# trx.net
KiCad netlist of a schematic drawn in EAGLE
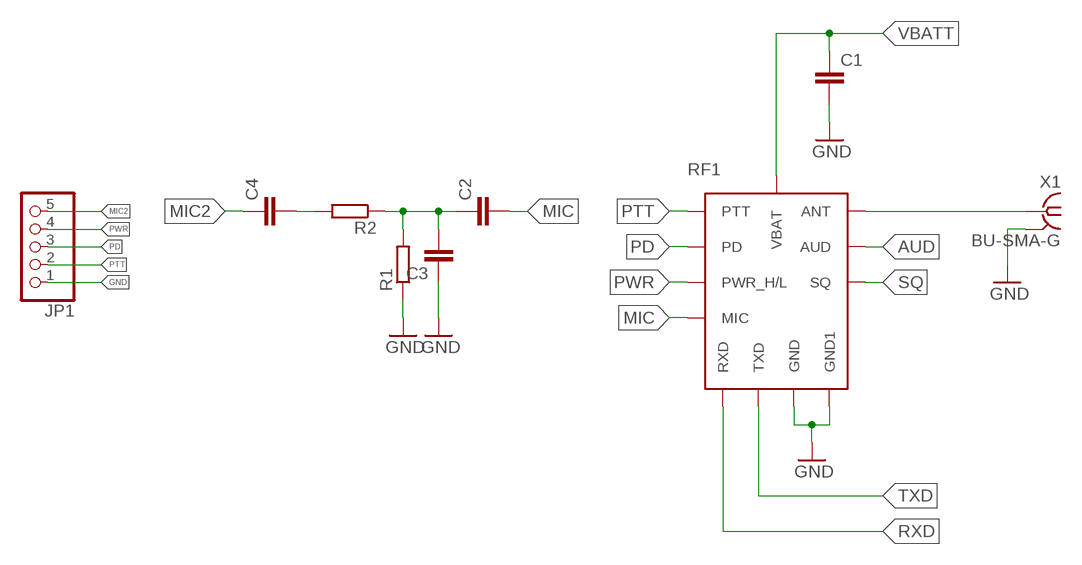
[diagram p0: schematic, sheet 1]

(export (version "E")
  (design (tool "Eeschema 10.0.6"))
  (components
    (comp (ref "C1")
      (value "C-EUC1206")
      (footprint "eagle-import:C1206")
      (libsource (lib "eagle-import") (part "C-EUC1206"))
    )
    (comp (ref "C2")
      (value "C-EUC1206")
      (footprint "eagle-import:C1206")
      (libsource (lib "eagle-import") (part "C-EUC1206"))
    )
    (comp (ref "C3")
      (value "C-EUC1206")
      (footprint "eagle-import:C1206")
      (libsource (lib "eagle-import") (part "C-EUC1206"))
    )
    (comp (ref "C4")
      (value "C-EUC1206")
      (footprint "eagle-import:C1206")
      (libsource (lib "eagle-import") (part "C-EUC1206"))
    )
    (comp (ref "JP1")
      (value "PINHD-1X5")
      (footprint "eagle-import:1X05")
      (libsource (lib "eagle-import") (part "PINHD-1X5"))
    )
    (comp (ref "R1")
      (value "R-EU_M1206")
      (footprint "eagle-import:M1206")
      (libsource (lib "eagle-import") (part "R-EU_M1206"))
    )
    (comp (ref "R2")
      (value "R-EU_M1206")
      (footprint "eagle-import:M1206")
      (libsource (lib "eagle-import") (part "R-EU_M1206"))
    )
    (comp (ref "RF1")
      (value "DRA818U")
      (footprint "eagle-import:DRA8XXZ")
      (libsource (lib "eagle-import") (part "DRA818U"))
    )
    (comp (ref "X1")
      (value "BU-SMA-G")
      (footprint "eagle-import:BU-SMA-G")
      (libsource (lib "eagle-import") (part "BU-SMA-G"))
    )
  )
  (nets
    (net (code "1") (name "AUD") (class "Default")
      (node (ref "RF1") (pin "P$3") (pinfunction "AUD_P$3") (pintype "bidirectional"))
    )
    (net (code "2") (name "GND") (class "Default")
      (node (ref "C1") (pin "2") (pinfunction "2_2") (pintype "passive"))
      (node (ref "C3") (pin "1") (pinfunction "1_1") (pintype "passive"))
      (node (ref "JP1") (pin "1") (pinfunction "1_1") (pintype "passive"))
      (node (ref "R1") (pin "1") (pinfunction "1_1") (pintype "passive"))
      (node (ref "RF1") (pin "P$10") (pinfunction "GND1_P$10") (pintype "bidirectional"))
      (node (ref "RF1") (pin "P$9") (pinfunction "GND_P$9") (pintype "bidirectional"))
      (node (ref "X1") (pin "2") (pinfunction "2_2") (pintype "passive"))
      (node (ref "X1") (pin "3") (pinfunction "2_3") (pintype "passive"))
      (node (ref "X1") (pin "4") (pinfunction "2_4") (pintype "passive"))
      (node (ref "X1") (pin "5") (pinfunction "2_5") (pintype "passive"))
    )
    (net (code "3") (name "MIC") (class "Default")
      (node (ref "C2") (pin "2") (pinfunction "2_2") (pintype "passive"))
      (node (ref "RF1") (pin "P$18") (pinfunction "MIC_P$18") (pintype "bidirectional"))
    )
    (net (code "4") (name "MIC2") (class "Default")
      (node (ref "C4") (pin "1") (pinfunction "1_1") (pintype "passive"))
      (node (ref "JP1") (pin "5") (pinfunction "5_5") (pintype "passive"))
    )
    (net (code "5") (name "Net-(C2-Pad1)") (class "Default")
      (node (ref "C2") (pin "1") (pinfunction "1_1") (pintype "passive"))
      (node (ref "C3") (pin "2") (pinfunction "2_2") (pintype "passive"))
      (node (ref "R1") (pin "2") (pinfunction "2_2") (pintype "passive"))
      (node (ref "R2") (pin "1") (pinfunction "1_1") (pintype "passive"))
    )
    (net (code "6") (name "Net-(C4-Pad2)") (class "Default")
      (node (ref "C4") (pin "2") (pinfunction "2_2") (pintype "passive"))
      (node (ref "R2") (pin "2") (pinfunction "2_2") (pintype "passive"))
    )
    (net (code "7") (name "Net-(RF1-ANT)") (class "Default")
      (node (ref "RF1") (pin "P$12") (pinfunction "ANT_P$12") (pintype "bidirectional"))
      (node (ref "X1") (pin "1") (pinfunction "1_1") (pintype "passive"))
    )
    (net (code "8") (name "PD") (class "Default")
      (node (ref "JP1") (pin "3") (pinfunction "3_3") (pintype "passive"))
      (node (ref "RF1") (pin "P$6") (pinfunction "PD_P$6") (pintype "bidirectional"))
    )
    (net (code "9") (name "PTT") (class "Default")
      (node (ref "JP1") (pin "2") (pinfunction "2_2") (pintype "passive"))
      (node (ref "RF1") (pin "P$5") (pinfunction "PTT_P$5") (pintype "bidirectional"))
    )
    (net (code "10") (name "PWR") (class "Default")
      (node (ref "JP1") (pin "4") (pinfunction "4_4") (pintype "passive"))
      (node (ref "RF1") (pin "P$7") (pinfunction "PWR_H/L_P$7") (pintype "bidirectional"))
    )
    (net (code "11") (name "RXD") (class "Default")
      (node (ref "RF1") (pin "P$16") (pinfunction "RXD_P$16") (pintype "bidirectional"))
    )
    (net (code "12") (name "SQ") (class "Default")
      (node (ref "RF1") (pin "P$1") (pinfunction "SQ_P$1") (pintype "bidirectional"))
    )
    (net (code "13") (name "TXD") (class "Default")
      (node (ref "RF1") (pin "P$17") (pinfunction "TXD_P$17") (pintype "bidirectional"))
    )
    (net (code "14") (name "VBATT") (class "Default")
      (node (ref "C1") (pin "1") (pinfunction "1_1") (pintype "passive"))
      (node (ref "RF1") (pin "P$8") (pinfunction "VBAT_P$8") (pintype "bidirectional"))
    )
  )
)
